# flotsamRowControllerv11a.net
KiCad netlist of a schematic drawn in EAGLE
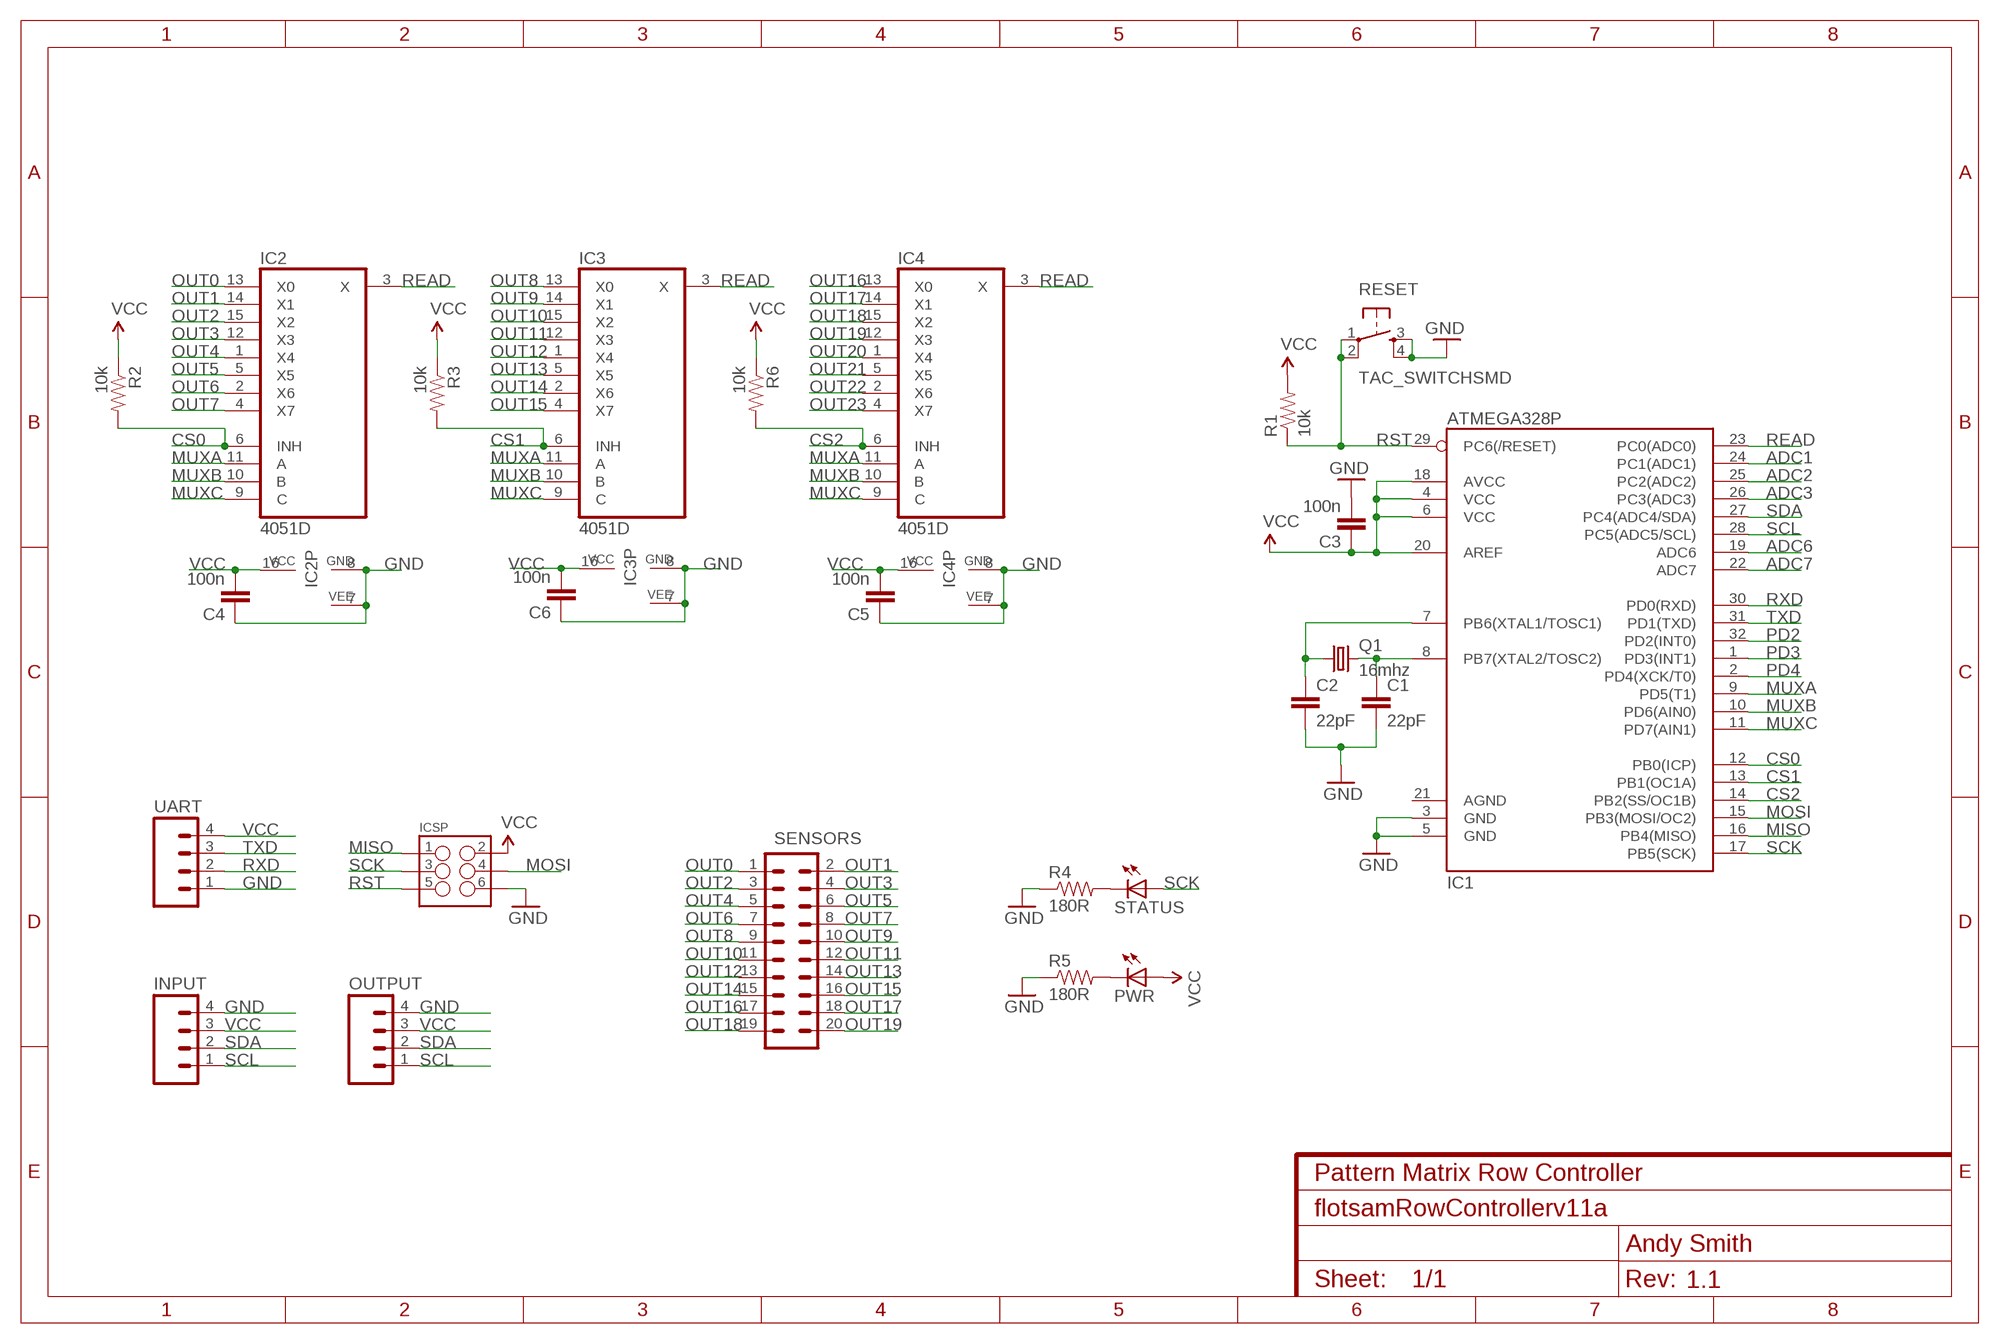
[diagram p0: schematic, sheet 1]

(export (version "E")
  (design (tool "Eeschema 10.0.6"))
  (components
    (comp (ref "C1")
      (value "22pF")
      (footprint "eagle-import:0805")
      (libsource (lib "eagle-import") (part "CAP0805"))
    )
    (comp (ref "C2")
      (value "22pF")
      (footprint "eagle-import:0805")
      (libsource (lib "eagle-import") (part "CAP0805"))
    )
    (comp (ref "C3")
      (value "100n")
      (footprint "eagle-import:0805")
      (libsource (lib "eagle-import") (part "CAP0805"))
    )
    (comp (ref "C4")
      (value "100n")
      (footprint "eagle-import:0805")
      (libsource (lib "eagle-import") (part "CAP0805"))
    )
    (comp (ref "C5")
      (value "100n")
      (footprint "eagle-import:0805")
      (libsource (lib "eagle-import") (part "CAP0805"))
    )
    (comp (ref "C6")
      (value "100n")
      (footprint "eagle-import:0805")
      (libsource (lib "eagle-import") (part "CAP0805"))
    )
    (comp (ref "IC1")
      (value "ATMEGA328P")
      (footprint "eagle-import:TQFP32-08")
      (libsource (lib "eagle-import") (part "ATMEGA328_SMT"))
    )
    (comp (ref "IC2")
      (value "4051D")
      (footprint "eagle-import:SO16")
      (libsource (lib "eagle-import") (part "4051D"))
    )
    (comp (ref "IC3")
      (value "4051D")
      (footprint "eagle-import:SO16")
      (libsource (lib "eagle-import") (part "4051D"))
    )
    (comp (ref "IC4")
      (value "4051D")
      (footprint "eagle-import:SO16")
      (libsource (lib "eagle-import") (part "4051D"))
    )
    (comp (ref "ICSP")
      (value "M03X2FEMALE")
      (footprint "eagle-import:2X3")
      (libsource (lib "eagle-import") (part "M03X2FEMALE"))
    )
    (comp (ref "INPUT")
      (value "M04LOCK")
      (footprint "eagle-import:1X04_LOCK")
      (libsource (lib "eagle-import") (part "M04LOCK"))
    )
    (comp (ref "OUTPUT")
      (value "M04LOCK")
      (footprint "eagle-import:1X04_LOCK")
      (libsource (lib "eagle-import") (part "M04LOCK"))
    )
    (comp (ref "PWR")
      (value "LEDSML0805")
      (footprint "eagle-import:SML0805")
      (libsource (lib "eagle-import") (part "LEDSML0805"))
    )
    (comp (ref "Q1")
      (value "16mhz")
      (footprint "eagle-import:HC49UP")
      (libsource (lib "eagle-import") (part "CRYSTALHC49UP"))
    )
    (comp (ref "R1")
      (value "10k")
      (footprint "eagle-import:0805")
      (libsource (lib "eagle-import") (part "RESISTOR0805-RES"))
    )
    (comp (ref "R2")
      (value "10k")
      (footprint "eagle-import:0805")
      (libsource (lib "eagle-import") (part "RESISTOR0805-RES"))
    )
    (comp (ref "R3")
      (value "10k")
      (footprint "eagle-import:0805")
      (libsource (lib "eagle-import") (part "RESISTOR0805-RES"))
    )
    (comp (ref "R4")
      (value "180R")
      (footprint "eagle-import:0805")
      (libsource (lib "eagle-import") (part "RESISTOR0805-RES"))
    )
    (comp (ref "R5")
      (value "180R")
      (footprint "eagle-import:0805")
      (libsource (lib "eagle-import") (part "RESISTOR0805-RES"))
    )
    (comp (ref "R6")
      (value "10k")
      (footprint "eagle-import:0805")
      (libsource (lib "eagle-import") (part "RESISTOR0805-RES"))
    )
    (comp (ref "RESET")
      (value "TAC_SWITCHSMD")
      (footprint "eagle-import:TACTILE-SWITCH-SMD")
      (libsource (lib "eagle-import") (part "TAC_SWITCHSMD"))
    )
    (comp (ref "SENSORS")
      (value "M10X22X10_LOCK")
      (footprint "eagle-import:2X10_LOCK")
      (libsource (lib "eagle-import") (part "M10X22X10_LOCK"))
    )
    (comp (ref "STATUS")
      (value "LEDSML0805")
      (footprint "eagle-import:SML0805")
      (libsource (lib "eagle-import") (part "LEDSML0805"))
    )
    (comp (ref "UART")
      (value "M04LOCK")
      (footprint "eagle-import:1X04_LOCK")
      (libsource (lib "eagle-import") (part "M04LOCK"))
    )
  )
  (nets
    (net (code "1") (name "/ADC1") (class "Default")
      (node (ref "IC1") (pin "24") (pinfunction "PC1(ADC1)_24") (pintype "bidirectional"))
    )
    (net (code "2") (name "/ADC2") (class "Default")
      (node (ref "IC1") (pin "25") (pinfunction "PC2(ADC2)_25") (pintype "bidirectional"))
    )
    (net (code "3") (name "/ADC3") (class "Default")
      (node (ref "IC1") (pin "26") (pinfunction "PC3(ADC3)_26") (pintype "bidirectional"))
    )
    (net (code "4") (name "/ADC6") (class "Default")
      (node (ref "IC1") (pin "19") (pinfunction "ADC6_19") (pintype "bidirectional"))
    )
    (net (code "5") (name "/ADC7") (class "Default")
      (node (ref "IC1") (pin "22") (pinfunction "ADC7_22") (pintype "bidirectional"))
    )
    (net (code "6") (name "/CS0") (class "Default")
      (node (ref "IC1") (pin "12") (pinfunction "PB0(ICP)_12") (pintype "bidirectional"))
      (node (ref "IC2") (pin "6") (pinfunction "INH_6") (pintype "input"))
      (node (ref "R2") (pin "2") (pinfunction "2_2") (pintype "passive"))
    )
    (net (code "7") (name "/CS1") (class "Default")
      (node (ref "IC1") (pin "13") (pinfunction "PB1(OC1A)_13") (pintype "bidirectional"))
      (node (ref "IC3") (pin "6") (pinfunction "INH_6") (pintype "input"))
      (node (ref "R3") (pin "2") (pinfunction "2_2") (pintype "passive"))
    )
    (net (code "8") (name "/CS2") (class "Default")
      (node (ref "IC1") (pin "14") (pinfunction "PB2(SS/OC1B)_14") (pintype "bidirectional"))
      (node (ref "IC4") (pin "6") (pinfunction "INH_6") (pintype "input"))
      (node (ref "R6") (pin "2") (pinfunction "2_2") (pintype "passive"))
    )
    (net (code "9") (name "/MISO") (class "Default")
      (node (ref "IC1") (pin "16") (pinfunction "PB4(MISO)_16") (pintype "bidirectional"))
      (node (ref "ICSP") (pin "1") (pinfunction "1_1") (pintype "bidirectional"))
    )
    (net (code "10") (name "/MOSI") (class "Default")
      (node (ref "IC1") (pin "15") (pinfunction "PB3(MOSI/OC2)_15") (pintype "bidirectional"))
      (node (ref "ICSP") (pin "4") (pinfunction "4_4") (pintype "bidirectional"))
    )
    (net (code "11") (name "/MUXA") (class "Default")
      (node (ref "IC1") (pin "9") (pinfunction "PD5(T1)_9") (pintype "bidirectional"))
      (node (ref "IC2") (pin "11") (pinfunction "A_11") (pintype "input"))
      (node (ref "IC3") (pin "11") (pinfunction "A_11") (pintype "input"))
      (node (ref "IC4") (pin "11") (pinfunction "A_11") (pintype "input"))
    )
    (net (code "12") (name "/MUXB") (class "Default")
      (node (ref "IC1") (pin "10") (pinfunction "PD6(AIN0)_10") (pintype "bidirectional"))
      (node (ref "IC2") (pin "10") (pinfunction "B_10") (pintype "input"))
      (node (ref "IC3") (pin "10") (pinfunction "B_10") (pintype "input"))
      (node (ref "IC4") (pin "10") (pinfunction "B_10") (pintype "input"))
    )
    (net (code "13") (name "/MUXC") (class "Default")
      (node (ref "IC1") (pin "11") (pinfunction "PD7(AIN1)_11") (pintype "bidirectional"))
      (node (ref "IC2") (pin "9") (pinfunction "C_9") (pintype "input"))
      (node (ref "IC3") (pin "9") (pinfunction "C_9") (pintype "input"))
      (node (ref "IC4") (pin "9") (pinfunction "C_9") (pintype "input"))
    )
    (net (code "14") (name "/OUT0") (class "Default")
      (node (ref "IC2") (pin "13") (pinfunction "X0_13") (pintype "bidirectional"))
      (node (ref "SENSORS") (pin "1") (pinfunction "1_1") (pintype "passive"))
    )
    (net (code "15") (name "/OUT1") (class "Default")
      (node (ref "IC2") (pin "14") (pinfunction "X1_14") (pintype "bidirectional"))
      (node (ref "SENSORS") (pin "2") (pinfunction "2_2") (pintype "passive"))
    )
    (net (code "16") (name "/OUT2") (class "Default")
      (node (ref "IC2") (pin "15") (pinfunction "X2_15") (pintype "bidirectional"))
      (node (ref "SENSORS") (pin "3") (pinfunction "3_3") (pintype "passive"))
    )
    (net (code "17") (name "/OUT3") (class "Default")
      (node (ref "IC2") (pin "12") (pinfunction "X3_12") (pintype "bidirectional"))
      (node (ref "SENSORS") (pin "4") (pinfunction "4_4") (pintype "passive"))
    )
    (net (code "18") (name "/OUT4") (class "Default")
      (node (ref "IC2") (pin "1") (pinfunction "X4_1") (pintype "bidirectional"))
      (node (ref "SENSORS") (pin "5") (pinfunction "5_5") (pintype "passive"))
    )
    (net (code "19") (name "/OUT5") (class "Default")
      (node (ref "IC2") (pin "5") (pinfunction "X5_5") (pintype "bidirectional"))
      (node (ref "SENSORS") (pin "6") (pinfunction "6_6") (pintype "passive"))
    )
    (net (code "20") (name "/OUT6") (class "Default")
      (node (ref "IC2") (pin "2") (pinfunction "X6_2") (pintype "bidirectional"))
      (node (ref "SENSORS") (pin "7") (pinfunction "7_7") (pintype "passive"))
    )
    (net (code "21") (name "/OUT7") (class "Default")
      (node (ref "IC2") (pin "4") (pinfunction "X7_4") (pintype "bidirectional"))
      (node (ref "SENSORS") (pin "8") (pinfunction "8_8") (pintype "passive"))
    )
    (net (code "22") (name "/OUT8") (class "Default")
      (node (ref "IC3") (pin "13") (pinfunction "X0_13") (pintype "bidirectional"))
      (node (ref "SENSORS") (pin "9") (pinfunction "9_9") (pintype "passive"))
    )
    (net (code "23") (name "/OUT9") (class "Default")
      (node (ref "IC3") (pin "14") (pinfunction "X1_14") (pintype "bidirectional"))
      (node (ref "SENSORS") (pin "10") (pinfunction "10_10") (pintype "passive"))
    )
    (net (code "24") (name "/OUT10") (class "Default")
      (node (ref "IC3") (pin "15") (pinfunction "X2_15") (pintype "bidirectional"))
      (node (ref "SENSORS") (pin "11") (pinfunction "11_11") (pintype "passive"))
    )
    (net (code "25") (name "/OUT11") (class "Default")
      (node (ref "IC3") (pin "12") (pinfunction "X3_12") (pintype "bidirectional"))
      (node (ref "SENSORS") (pin "12") (pinfunction "12_12") (pintype "passive"))
    )
    (net (code "26") (name "/OUT12") (class "Default")
      (node (ref "IC3") (pin "1") (pinfunction "X4_1") (pintype "bidirectional"))
      (node (ref "SENSORS") (pin "13") (pinfunction "13_13") (pintype "passive"))
    )
    (net (code "27") (name "/OUT13") (class "Default")
      (node (ref "IC3") (pin "5") (pinfunction "X5_5") (pintype "bidirectional"))
      (node (ref "SENSORS") (pin "14") (pinfunction "14_14") (pintype "passive"))
    )
    (net (code "28") (name "/OUT14") (class "Default")
      (node (ref "IC3") (pin "2") (pinfunction "X6_2") (pintype "bidirectional"))
      (node (ref "SENSORS") (pin "15") (pinfunction "15_15") (pintype "passive"))
    )
    (net (code "29") (name "/OUT15") (class "Default")
      (node (ref "IC3") (pin "4") (pinfunction "X7_4") (pintype "bidirectional"))
      (node (ref "SENSORS") (pin "16") (pinfunction "16_16") (pintype "passive"))
    )
    (net (code "30") (name "/OUT16") (class "Default")
      (node (ref "IC4") (pin "13") (pinfunction "X0_13") (pintype "bidirectional"))
      (node (ref "SENSORS") (pin "17") (pinfunction "17_17") (pintype "passive"))
    )
    (net (code "31") (name "/OUT17") (class "Default")
      (node (ref "IC4") (pin "14") (pinfunction "X1_14") (pintype "bidirectional"))
      (node (ref "SENSORS") (pin "18") (pinfunction "18_18") (pintype "passive"))
    )
    (net (code "32") (name "/OUT18") (class "Default")
      (node (ref "IC4") (pin "15") (pinfunction "X2_15") (pintype "bidirectional"))
      (node (ref "SENSORS") (pin "19") (pinfunction "19_19") (pintype "passive"))
    )
    (net (code "33") (name "/OUT19") (class "Default")
      (node (ref "IC4") (pin "12") (pinfunction "X3_12") (pintype "bidirectional"))
      (node (ref "SENSORS") (pin "20") (pinfunction "20_20") (pintype "passive"))
    )
    (net (code "34") (name "/OUT20") (class "Default")
      (node (ref "IC4") (pin "1") (pinfunction "X4_1") (pintype "bidirectional"))
    )
    (net (code "35") (name "/OUT21") (class "Default")
      (node (ref "IC4") (pin "5") (pinfunction "X5_5") (pintype "bidirectional"))
    )
    (net (code "36") (name "/OUT22") (class "Default")
      (node (ref "IC4") (pin "2") (pinfunction "X6_2") (pintype "bidirectional"))
    )
    (net (code "37") (name "/OUT23") (class "Default")
      (node (ref "IC4") (pin "4") (pinfunction "X7_4") (pintype "bidirectional"))
    )
    (net (code "38") (name "/PD2") (class "Default")
      (node (ref "IC1") (pin "32") (pinfunction "PD2(INT0)_32") (pintype "bidirectional"))
    )
    (net (code "39") (name "/PD3") (class "Default")
      (node (ref "IC1") (pin "1") (pinfunction "PD3(INT1)_1") (pintype "bidirectional"))
    )
    (net (code "40") (name "/PD4") (class "Default")
      (node (ref "IC1") (pin "2") (pinfunction "PD4(XCK/T0)_2") (pintype "bidirectional"))
    )
    (net (code "41") (name "/READ") (class "Default")
      (node (ref "IC1") (pin "23") (pinfunction "PC0(ADC0)_23") (pintype "bidirectional"))
      (node (ref "IC2") (pin "3") (pinfunction "X_3") (pintype "bidirectional"))
      (node (ref "IC3") (pin "3") (pinfunction "X_3") (pintype "bidirectional"))
      (node (ref "IC4") (pin "3") (pinfunction "X_3") (pintype "bidirectional"))
    )
    (net (code "42") (name "/RST") (class "Default")
      (node (ref "IC1") (pin "29") (pinfunction "PC6(/RESET)_29") (pintype "bidirectional"))
      (node (ref "ICSP") (pin "5") (pinfunction "5_5") (pintype "bidirectional"))
      (node (ref "R1") (pin "1") (pinfunction "1_1") (pintype "passive"))
      (node (ref "RESET") (pin "1") (pinfunction "1_1") (pintype "passive"))
      (node (ref "RESET") (pin "2") (pinfunction "2_2") (pintype "passive"))
    )
    (net (code "43") (name "/RXD") (class "Default")
      (node (ref "IC1") (pin "30") (pinfunction "PD0(RXD)_30") (pintype "bidirectional"))
      (node (ref "UART") (pin "2") (pinfunction "2_2") (pintype "passive"))
    )
    (net (code "44") (name "/SCK") (class "Default")
      (node (ref "IC1") (pin "17") (pinfunction "PB5(SCK)_17") (pintype "bidirectional"))
      (node (ref "ICSP") (pin "3") (pinfunction "3_3") (pintype "bidirectional"))
      (node (ref "STATUS") (pin "A") (pinfunction "A_A") (pintype "passive"))
    )
    (net (code "45") (name "/SCL") (class "Default")
      (node (ref "IC1") (pin "28") (pinfunction "PC5(ADC5/SCL)_28") (pintype "bidirectional"))
      (node (ref "INPUT") (pin "1") (pinfunction "1_1") (pintype "passive"))
      (node (ref "OUTPUT") (pin "1") (pinfunction "1_1") (pintype "passive"))
    )
    (net (code "46") (name "/SDA") (class "Default")
      (node (ref "IC1") (pin "27") (pinfunction "PC4(ADC4/SDA)_27") (pintype "bidirectional"))
      (node (ref "INPUT") (pin "2") (pinfunction "2_2") (pintype "passive"))
      (node (ref "OUTPUT") (pin "2") (pinfunction "2_2") (pintype "passive"))
    )
    (net (code "47") (name "/TXD") (class "Default")
      (node (ref "IC1") (pin "31") (pinfunction "PD1(TXD)_31") (pintype "bidirectional"))
      (node (ref "UART") (pin "3") (pinfunction "3_3") (pintype "passive"))
    )
    (net (code "48") (name "GND") (class "Default")
      (node (ref "C1") (pin "2") (pinfunction "2_2") (pintype "passive"))
      (node (ref "C2") (pin "2") (pinfunction "2_2") (pintype "passive"))
      (node (ref "C3") (pin "2") (pinfunction "2_2") (pintype "passive"))
      (node (ref "C4") (pin "1") (pinfunction "1_1") (pintype "passive"))
      (node (ref "C5") (pin "1") (pinfunction "1_1") (pintype "passive"))
      (node (ref "C6") (pin "1") (pinfunction "1_1") (pintype "passive"))
      (node (ref "IC1") (pin "3") (pinfunction "GND_3") (pintype "bidirectional"))
      (node (ref "IC1") (pin "5") (pinfunction "GND_5") (pintype "bidirectional"))
      (node (ref "IC2") (pin "7") (pinfunction "VEE_7") (pintype "power_in"))
      (node (ref "IC2") (pin "8") (pinfunction "GND_8") (pintype "power_in"))
      (node (ref "IC3") (pin "7") (pinfunction "VEE_7") (pintype "power_in"))
      (node (ref "IC3") (pin "8") (pinfunction "GND_8") (pintype "power_in"))
      (node (ref "IC4") (pin "7") (pinfunction "VEE_7") (pintype "power_in"))
      (node (ref "IC4") (pin "8") (pinfunction "GND_8") (pintype "power_in"))
      (node (ref "ICSP") (pin "6") (pinfunction "6_6") (pintype "bidirectional"))
      (node (ref "INPUT") (pin "4") (pinfunction "4_4") (pintype "passive"))
      (node (ref "OUTPUT") (pin "4") (pinfunction "4_4") (pintype "passive"))
      (node (ref "R4") (pin "1") (pinfunction "1_1") (pintype "passive"))
      (node (ref "R5") (pin "1") (pinfunction "1_1") (pintype "passive"))
      (node (ref "RESET") (pin "3") (pinfunction "3_3") (pintype "passive"))
      (node (ref "RESET") (pin "4") (pinfunction "4_4") (pintype "passive"))
      (node (ref "UART") (pin "1") (pinfunction "1_1") (pintype "passive"))
    )
    (net (code "49") (name "Net-(IC1-PB6(XTAL1{slash}TOSC1))") (class "Default")
      (node (ref "C2") (pin "1") (pinfunction "1_1") (pintype "passive"))
      (node (ref "IC1") (pin "7") (pinfunction "PB6(XTAL1/TOSC1)_7") (pintype "bidirectional"))
      (node (ref "Q1") (pin "1") (pinfunction "1_1") (pintype "passive"))
    )
    (net (code "50") (name "Net-(IC1-PB7(XTAL2{slash}TOSC2))") (class "Default")
      (node (ref "C1") (pin "1") (pinfunction "1_1") (pintype "passive"))
      (node (ref "IC1") (pin "8") (pinfunction "PB7(XTAL2/TOSC2)_8") (pintype "bidirectional"))
      (node (ref "Q1") (pin "2") (pinfunction "2_2") (pintype "passive"))
    )
    (net (code "51") (name "Net-(PWR-PadC)") (class "Default")
      (node (ref "PWR") (pin "C") (pinfunction "C_C") (pintype "passive"))
      (node (ref "R5") (pin "2") (pinfunction "2_2") (pintype "passive"))
    )
    (net (code "52") (name "Net-(R4-Pad2)") (class "Default")
      (node (ref "R4") (pin "2") (pinfunction "2_2") (pintype "passive"))
      (node (ref "STATUS") (pin "C") (pinfunction "C_C") (pintype "passive"))
    )
    (net (code "53") (name "VCC") (class "Default")
      (node (ref "C3") (pin "1") (pinfunction "1_1") (pintype "passive"))
      (node (ref "C4") (pin "2") (pinfunction "2_2") (pintype "passive"))
      (node (ref "C5") (pin "2") (pinfunction "2_2") (pintype "passive"))
      (node (ref "C6") (pin "2") (pinfunction "2_2") (pintype "passive"))
      (node (ref "IC1") (pin "18") (pinfunction "AVCC_18") (pintype "bidirectional"))
      (node (ref "IC1") (pin "20") (pinfunction "AREF_20") (pintype "bidirectional"))
      (node (ref "IC1") (pin "4") (pinfunction "VCC_4") (pintype "bidirectional"))
      (node (ref "IC1") (pin "6") (pinfunction "VCC_6") (pintype "bidirectional"))
      (node (ref "IC2") (pin "16") (pinfunction "VCC_16") (pintype "power_in"))
      (node (ref "IC3") (pin "16") (pinfunction "VCC_16") (pintype "power_in"))
      (node (ref "IC4") (pin "16") (pinfunction "VCC_16") (pintype "power_in"))
      (node (ref "ICSP") (pin "2") (pinfunction "2_2") (pintype "bidirectional"))
      (node (ref "INPUT") (pin "3") (pinfunction "3_3") (pintype "passive"))
      (node (ref "OUTPUT") (pin "3") (pinfunction "3_3") (pintype "passive"))
      (node (ref "PWR") (pin "A") (pinfunction "A_A") (pintype "passive"))
      (node (ref "R1") (pin "2") (pinfunction "2_2") (pintype "passive"))
      (node (ref "R2") (pin "1") (pinfunction "1_1") (pintype "passive"))
      (node (ref "R3") (pin "1") (pinfunction "1_1") (pintype "passive"))
      (node (ref "R6") (pin "1") (pinfunction "1_1") (pintype "passive"))
      (node (ref "UART") (pin "4") (pinfunction "4_4") (pintype "passive"))
    )
    (net (code "54") (name "unconnected-(IC1-AGND-Pad21)") (class "Default")
      (node (ref "IC1") (pin "21") (pinfunction "AGND_21") (pintype "bidirectional"))
    )
  )
)
